# spacing.net
KiCad netlist of a schematic drawn in EAGLE
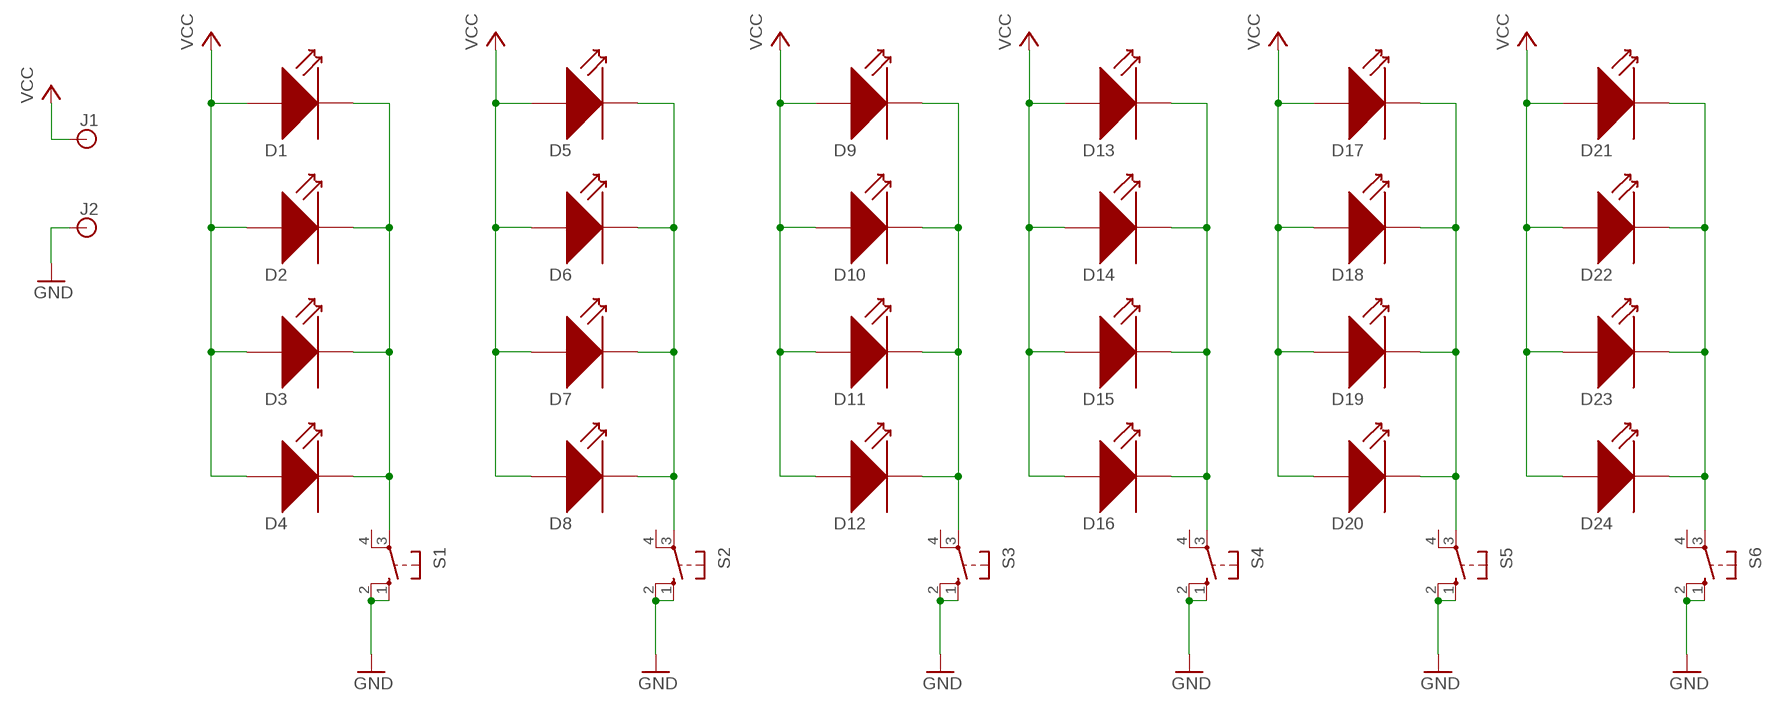
[diagram p0: schematic, sheet 1]

(export (version "E")
  (design (tool "Eeschema 10.0.6"))
  (components
    (comp (ref "D1")
      (value "NVSLE21AT")
      (footprint "eagle-import:NVSLE21AT")
      (libsource (lib "eagle-import") (part "NVSLE21AT"))
    )
    (comp (ref "D2")
      (value "NVSLE21AT")
      (footprint "eagle-import:NVSLE21AT")
      (libsource (lib "eagle-import") (part "NVSLE21AT"))
    )
    (comp (ref "D3")
      (value "NVSLE21AT")
      (footprint "eagle-import:NVSLE21AT")
      (libsource (lib "eagle-import") (part "NVSLE21AT"))
    )
    (comp (ref "D4")
      (value "NVSLE21AT")
      (footprint "eagle-import:NVSLE21AT")
      (libsource (lib "eagle-import") (part "NVSLE21AT"))
    )
    (comp (ref "D5")
      (value "NVSLE21AT")
      (footprint "eagle-import:NVSLE21AT")
      (libsource (lib "eagle-import") (part "NVSLE21AT"))
    )
    (comp (ref "D6")
      (value "NVSLE21AT")
      (footprint "eagle-import:NVSLE21AT")
      (libsource (lib "eagle-import") (part "NVSLE21AT"))
    )
    (comp (ref "D7")
      (value "NVSLE21AT")
      (footprint "eagle-import:NVSLE21AT")
      (libsource (lib "eagle-import") (part "NVSLE21AT"))
    )
    (comp (ref "D8")
      (value "NVSLE21AT")
      (footprint "eagle-import:NVSLE21AT")
      (libsource (lib "eagle-import") (part "NVSLE21AT"))
    )
    (comp (ref "D9")
      (value "NVSLE21AT")
      (footprint "eagle-import:NVSLE21AT")
      (libsource (lib "eagle-import") (part "NVSLE21AT"))
    )
    (comp (ref "D10")
      (value "NVSLE21AT")
      (footprint "eagle-import:NVSLE21AT")
      (libsource (lib "eagle-import") (part "NVSLE21AT"))
    )
    (comp (ref "D11")
      (value "NVSLE21AT")
      (footprint "eagle-import:NVSLE21AT")
      (libsource (lib "eagle-import") (part "NVSLE21AT"))
    )
    (comp (ref "D12")
      (value "NVSLE21AT")
      (footprint "eagle-import:NVSLE21AT")
      (libsource (lib "eagle-import") (part "NVSLE21AT"))
    )
    (comp (ref "D13")
      (value "NVSLE21AT")
      (footprint "eagle-import:NVSLE21AT")
      (libsource (lib "eagle-import") (part "NVSLE21AT"))
    )
    (comp (ref "D14")
      (value "NVSLE21AT")
      (footprint "eagle-import:NVSLE21AT")
      (libsource (lib "eagle-import") (part "NVSLE21AT"))
    )
    (comp (ref "D15")
      (value "NVSLE21AT")
      (footprint "eagle-import:NVSLE21AT")
      (libsource (lib "eagle-import") (part "NVSLE21AT"))
    )
    (comp (ref "D16")
      (value "NVSLE21AT")
      (footprint "eagle-import:NVSLE21AT")
      (libsource (lib "eagle-import") (part "NVSLE21AT"))
    )
    (comp (ref "D17")
      (value "NVSLE21AT")
      (footprint "eagle-import:NVSLE21AT")
      (libsource (lib "eagle-import") (part "NVSLE21AT"))
    )
    (comp (ref "D18")
      (value "NVSLE21AT")
      (footprint "eagle-import:NVSLE21AT")
      (libsource (lib "eagle-import") (part "NVSLE21AT"))
    )
    (comp (ref "D19")
      (value "NVSLE21AT")
      (footprint "eagle-import:NVSLE21AT")
      (libsource (lib "eagle-import") (part "NVSLE21AT"))
    )
    (comp (ref "D20")
      (value "NVSLE21AT")
      (footprint "eagle-import:NVSLE21AT")
      (libsource (lib "eagle-import") (part "NVSLE21AT"))
    )
    (comp (ref "D21")
      (value "NVSLE21AT")
      (footprint "eagle-import:NVSLE21AT")
      (libsource (lib "eagle-import") (part "NVSLE21AT"))
    )
    (comp (ref "D22")
      (value "NVSLE21AT")
      (footprint "eagle-import:NVSLE21AT")
      (libsource (lib "eagle-import") (part "NVSLE21AT"))
    )
    (comp (ref "D23")
      (value "NVSLE21AT")
      (footprint "eagle-import:NVSLE21AT")
      (libsource (lib "eagle-import") (part "NVSLE21AT"))
    )
    (comp (ref "D24")
      (value "NVSLE21AT")
      (footprint "eagle-import:NVSLE21AT")
      (libsource (lib "eagle-import") (part "NVSLE21AT"))
    )
    (comp (ref "J1")
      (value "BANANA_CONN")
      (footprint "eagle-import:BANANA_CONN")
      (libsource (lib "eagle-import") (part "BANANA_CONN"))
    )
    (comp (ref "J2")
      (value "BANANA_CONN")
      (footprint "eagle-import:BANANA_CONN")
      (libsource (lib "eagle-import") (part "BANANA_CONN"))
    )
    (comp (ref "S1")
      (value "10-XX")
      (footprint "eagle-import:B3F-10XX")
      (fields (field (name "MPN") "B3F-1000"))
      (libsource (lib "eagle-import") (part "10-XX"))
    )
    (comp (ref "S2")
      (value "10-XX")
      (footprint "eagle-import:B3F-10XX")
      (fields (field (name "MPN") "B3F-1000"))
      (libsource (lib "eagle-import") (part "10-XX"))
    )
    (comp (ref "S3")
      (value "10-XX")
      (footprint "eagle-import:B3F-10XX")
      (fields (field (name "MPN") "B3F-1000"))
      (libsource (lib "eagle-import") (part "10-XX"))
    )
    (comp (ref "S4")
      (value "10-XX")
      (footprint "eagle-import:B3F-10XX")
      (fields (field (name "MPN") "B3F-1000"))
      (libsource (lib "eagle-import") (part "10-XX"))
    )
    (comp (ref "S5")
      (value "10-XX")
      (footprint "eagle-import:B3F-10XX")
      (fields (field (name "MPN") "B3F-1000"))
      (libsource (lib "eagle-import") (part "10-XX"))
    )
    (comp (ref "S6")
      (value "10-XX")
      (footprint "eagle-import:B3F-10XX")
      (fields (field (name "MPN") "B3F-1000"))
      (libsource (lib "eagle-import") (part "10-XX"))
    )
  )
  (nets
    (net (code "1") (name "GND") (class "Default")
      (node (ref "J2") (pin "P$1") (pinfunction "1_P$1") (pintype "passive"))
      (node (ref "S1") (pin "1") (pinfunction "S_1") (pintype "passive"))
      (node (ref "S1") (pin "2") (pinfunction "S1_2") (pintype "passive"))
      (node (ref "S2") (pin "1") (pinfunction "S_1") (pintype "passive"))
      (node (ref "S2") (pin "2") (pinfunction "S1_2") (pintype "passive"))
      (node (ref "S3") (pin "1") (pinfunction "S_1") (pintype "passive"))
      (node (ref "S3") (pin "2") (pinfunction "S1_2") (pintype "passive"))
      (node (ref "S4") (pin "1") (pinfunction "S_1") (pintype "passive"))
      (node (ref "S4") (pin "2") (pinfunction "S1_2") (pintype "passive"))
      (node (ref "S5") (pin "1") (pinfunction "S_1") (pintype "passive"))
      (node (ref "S5") (pin "2") (pinfunction "S1_2") (pintype "passive"))
      (node (ref "S6") (pin "1") (pinfunction "S_1") (pintype "passive"))
      (node (ref "S6") (pin "2") (pinfunction "S1_2") (pintype "passive"))
    )
    (net (code "2") (name "Net-(D1-CATHODE)") (class "Default")
      (node (ref "D1") (pin "P$1") (pinfunction "CATHODE_P$1") (pintype "bidirectional"))
      (node (ref "D2") (pin "P$1") (pinfunction "CATHODE_P$1") (pintype "bidirectional"))
      (node (ref "D3") (pin "P$1") (pinfunction "CATHODE_P$1") (pintype "bidirectional"))
      (node (ref "D4") (pin "P$1") (pinfunction "CATHODE_P$1") (pintype "bidirectional"))
      (node (ref "S1") (pin "3") (pinfunction "P_3") (pintype "passive"))
    )
    (net (code "3") (name "Net-(D5-CATHODE)") (class "Default")
      (node (ref "D5") (pin "P$1") (pinfunction "CATHODE_P$1") (pintype "bidirectional"))
      (node (ref "D6") (pin "P$1") (pinfunction "CATHODE_P$1") (pintype "bidirectional"))
      (node (ref "D7") (pin "P$1") (pinfunction "CATHODE_P$1") (pintype "bidirectional"))
      (node (ref "D8") (pin "P$1") (pinfunction "CATHODE_P$1") (pintype "bidirectional"))
      (node (ref "S2") (pin "3") (pinfunction "P_3") (pintype "passive"))
    )
    (net (code "4") (name "Net-(D10-CATHODE)") (class "Default")
      (node (ref "D10") (pin "P$1") (pinfunction "CATHODE_P$1") (pintype "bidirectional"))
      (node (ref "D11") (pin "P$1") (pinfunction "CATHODE_P$1") (pintype "bidirectional"))
      (node (ref "D12") (pin "P$1") (pinfunction "CATHODE_P$1") (pintype "bidirectional"))
      (node (ref "D9") (pin "P$1") (pinfunction "CATHODE_P$1") (pintype "bidirectional"))
      (node (ref "S3") (pin "3") (pinfunction "P_3") (pintype "passive"))
    )
    (net (code "5") (name "Net-(D13-CATHODE)") (class "Default")
      (node (ref "D13") (pin "P$1") (pinfunction "CATHODE_P$1") (pintype "bidirectional"))
      (node (ref "D14") (pin "P$1") (pinfunction "CATHODE_P$1") (pintype "bidirectional"))
      (node (ref "D15") (pin "P$1") (pinfunction "CATHODE_P$1") (pintype "bidirectional"))
      (node (ref "D16") (pin "P$1") (pinfunction "CATHODE_P$1") (pintype "bidirectional"))
      (node (ref "S4") (pin "3") (pinfunction "P_3") (pintype "passive"))
    )
    (net (code "6") (name "Net-(D17-CATHODE)") (class "Default")
      (node (ref "D17") (pin "P$1") (pinfunction "CATHODE_P$1") (pintype "bidirectional"))
      (node (ref "D18") (pin "P$1") (pinfunction "CATHODE_P$1") (pintype "bidirectional"))
      (node (ref "D19") (pin "P$1") (pinfunction "CATHODE_P$1") (pintype "bidirectional"))
      (node (ref "D20") (pin "P$1") (pinfunction "CATHODE_P$1") (pintype "bidirectional"))
      (node (ref "S5") (pin "3") (pinfunction "P_3") (pintype "passive"))
    )
    (net (code "7") (name "Net-(D21-CATHODE)") (class "Default")
      (node (ref "D21") (pin "P$1") (pinfunction "CATHODE_P$1") (pintype "bidirectional"))
      (node (ref "D22") (pin "P$1") (pinfunction "CATHODE_P$1") (pintype "bidirectional"))
      (node (ref "D23") (pin "P$1") (pinfunction "CATHODE_P$1") (pintype "bidirectional"))
      (node (ref "D24") (pin "P$1") (pinfunction "CATHODE_P$1") (pintype "bidirectional"))
      (node (ref "S6") (pin "3") (pinfunction "P_3") (pintype "passive"))
    )
    (net (code "8") (name "VCC") (class "Default")
      (node (ref "D1") (pin "P$2") (pinfunction "ANODE_P$2") (pintype "bidirectional"))
      (node (ref "D10") (pin "P$2") (pinfunction "ANODE_P$2") (pintype "bidirectional"))
      (node (ref "D11") (pin "P$2") (pinfunction "ANODE_P$2") (pintype "bidirectional"))
      (node (ref "D12") (pin "P$2") (pinfunction "ANODE_P$2") (pintype "bidirectional"))
      (node (ref "D13") (pin "P$2") (pinfunction "ANODE_P$2") (pintype "bidirectional"))
      (node (ref "D14") (pin "P$2") (pinfunction "ANODE_P$2") (pintype "bidirectional"))
      (node (ref "D15") (pin "P$2") (pinfunction "ANODE_P$2") (pintype "bidirectional"))
      (node (ref "D16") (pin "P$2") (pinfunction "ANODE_P$2") (pintype "bidirectional"))
      (node (ref "D17") (pin "P$2") (pinfunction "ANODE_P$2") (pintype "bidirectional"))
      (node (ref "D18") (pin "P$2") (pinfunction "ANODE_P$2") (pintype "bidirectional"))
      (node (ref "D19") (pin "P$2") (pinfunction "ANODE_P$2") (pintype "bidirectional"))
      (node (ref "D2") (pin "P$2") (pinfunction "ANODE_P$2") (pintype "bidirectional"))
      (node (ref "D20") (pin "P$2") (pinfunction "ANODE_P$2") (pintype "bidirectional"))
      (node (ref "D21") (pin "P$2") (pinfunction "ANODE_P$2") (pintype "bidirectional"))
      (node (ref "D22") (pin "P$2") (pinfunction "ANODE_P$2") (pintype "bidirectional"))
      (node (ref "D23") (pin "P$2") (pinfunction "ANODE_P$2") (pintype "bidirectional"))
      (node (ref "D24") (pin "P$2") (pinfunction "ANODE_P$2") (pintype "bidirectional"))
      (node (ref "D3") (pin "P$2") (pinfunction "ANODE_P$2") (pintype "bidirectional"))
      (node (ref "D4") (pin "P$2") (pinfunction "ANODE_P$2") (pintype "bidirectional"))
      (node (ref "D5") (pin "P$2") (pinfunction "ANODE_P$2") (pintype "bidirectional"))
      (node (ref "D6") (pin "P$2") (pinfunction "ANODE_P$2") (pintype "bidirectional"))
      (node (ref "D7") (pin "P$2") (pinfunction "ANODE_P$2") (pintype "bidirectional"))
      (node (ref "D8") (pin "P$2") (pinfunction "ANODE_P$2") (pintype "bidirectional"))
      (node (ref "D9") (pin "P$2") (pinfunction "ANODE_P$2") (pintype "bidirectional"))
      (node (ref "J1") (pin "P$1") (pinfunction "1_P$1") (pintype "passive"))
    )
    (net (code "9") (name "unconnected-(S1-P1-Pad4)") (class "Default")
      (node (ref "S1") (pin "4") (pinfunction "P1_4") (pintype "passive"))
    )
    (net (code "10") (name "unconnected-(S2-P1-Pad4)") (class "Default")
      (node (ref "S2") (pin "4") (pinfunction "P1_4") (pintype "passive"))
    )
    (net (code "11") (name "unconnected-(S3-P1-Pad4)") (class "Default")
      (node (ref "S3") (pin "4") (pinfunction "P1_4") (pintype "passive"))
    )
    (net (code "12") (name "unconnected-(S4-P1-Pad4)") (class "Default")
      (node (ref "S4") (pin "4") (pinfunction "P1_4") (pintype "passive"))
    )
    (net (code "13") (name "unconnected-(S5-P1-Pad4)") (class "Default")
      (node (ref "S5") (pin "4") (pinfunction "P1_4") (pintype "passive"))
    )
    (net (code "14") (name "unconnected-(S6-P1-Pad4)") (class "Default")
      (node (ref "S6") (pin "4") (pinfunction "P1_4") (pintype "passive"))
    )
  )
)
